# tinynano.net
KiCad netlist of a schematic drawn in Altium Designer
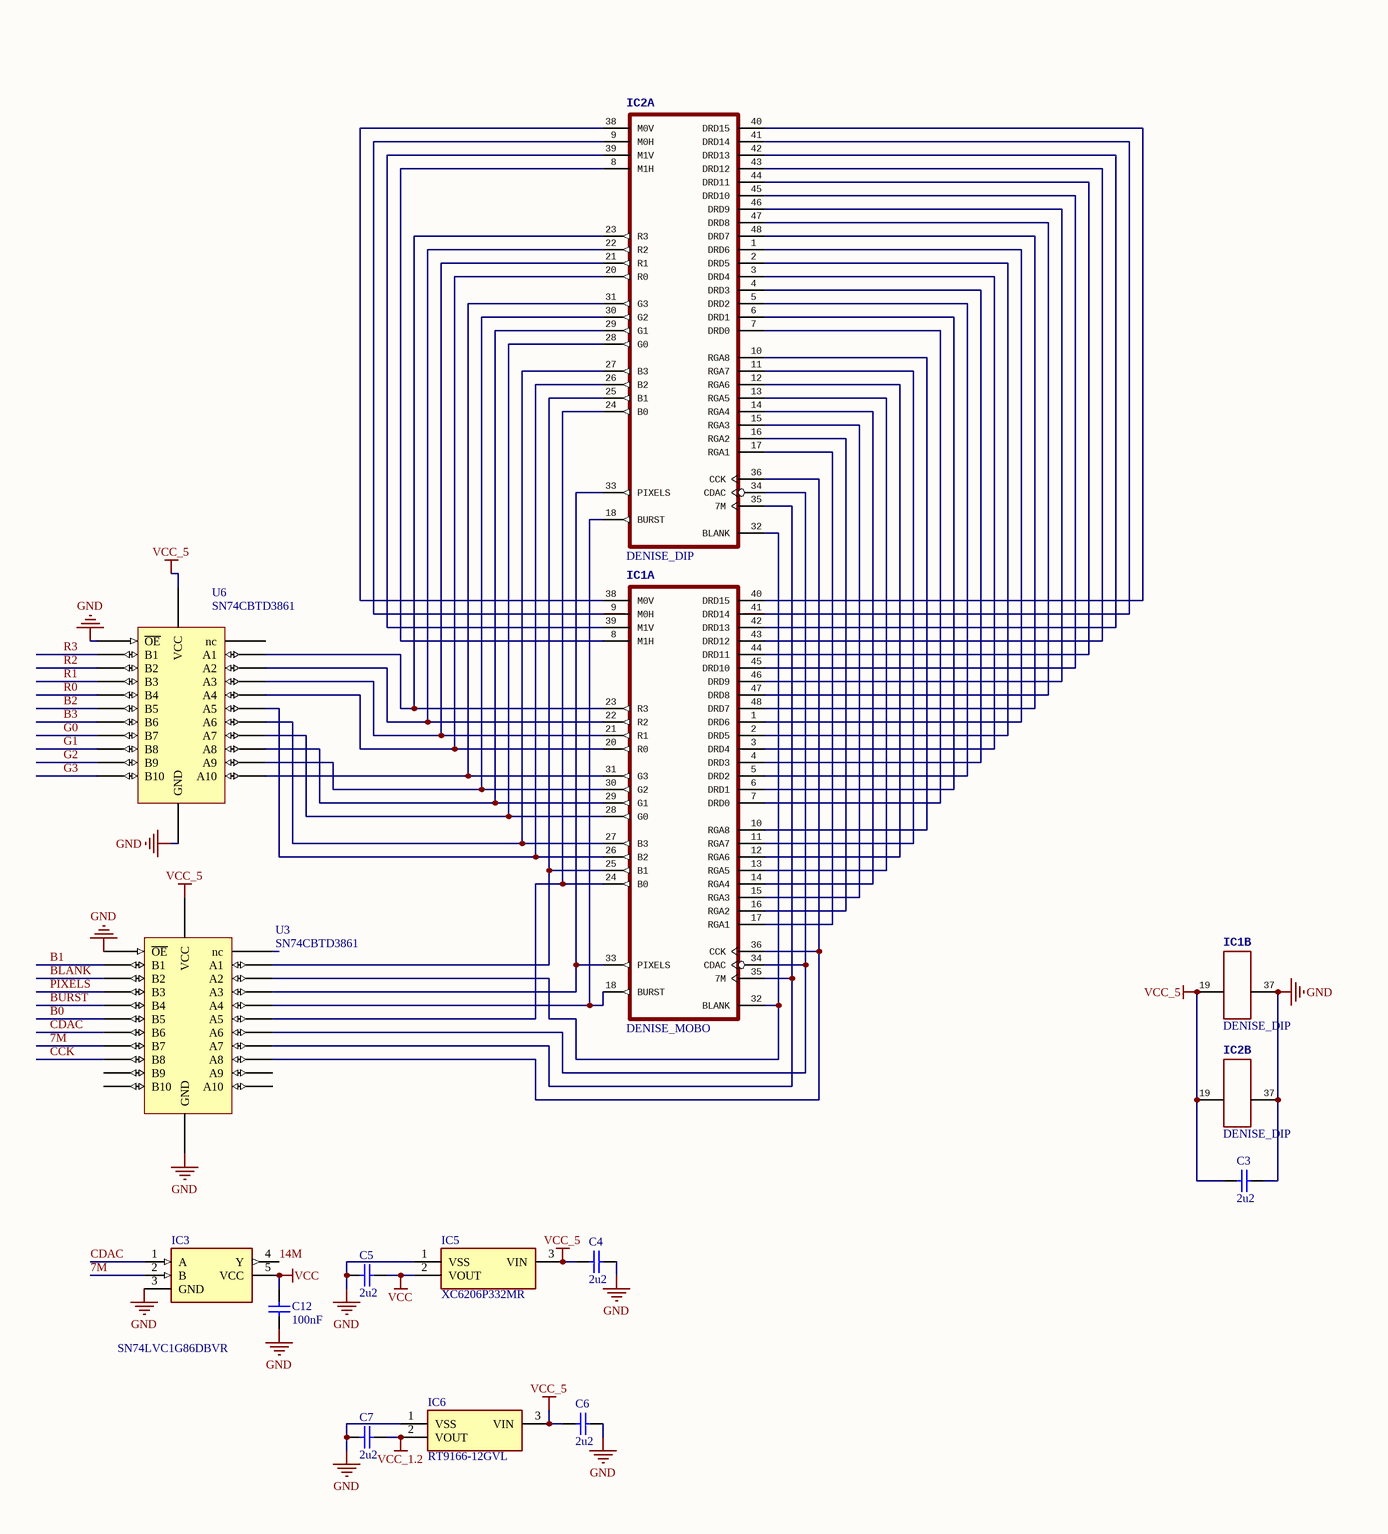
[diagram p0: tinynano.SchDoc, left]
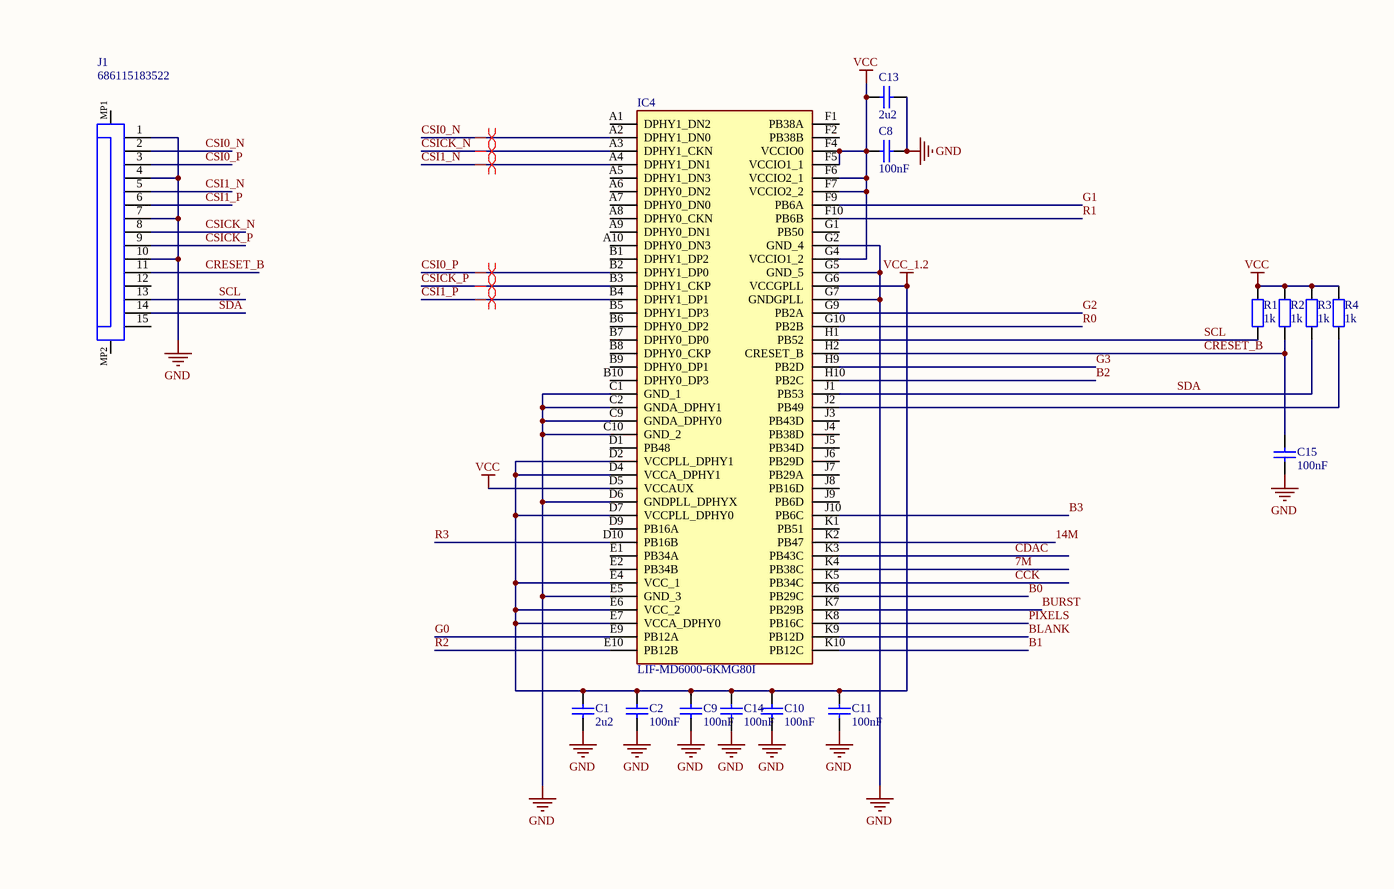
[diagram p1: tinynano.SchDoc, right]

(export (version "E")
  (design (tool "Eeschema 10.0.6"))
  (components
    (comp (ref "C1")
      (value "2u2")
      (footprint "1608[0603]")
      (description "Capacitor (Semiconductor SIM Model)")
      (fields (field (name "Comment") "Cap Semi") (field (name "PUBLISHER") "Altium Limited"))
      (libsource (lib "Miscellaneous Devices") (part "Cap Semi"))
    )
    (comp (ref "C2")
      (value "100nF")
      (footprint "0402")
      (description "Capacitor (Semiconductor SIM Model)")
      (fields (field (name "Comment") "Cap Semi") (field (name "PUBLISHER") "Altium Limited"))
      (libsource (lib "Miscellaneous Devices") (part "Cap Semi"))
    )
    (comp (ref "C3")
      (value "2u2")
      (footprint "1608[0603]")
      (description "Capacitor (Semiconductor SIM Model)")
      (fields (field (name "Comment") "Cap Semi") (field (name "PUBLISHER") "Altium Limited"))
      (libsource (lib "Miscellaneous Devices") (part "Cap Semi"))
    )
    (comp (ref "C4")
      (value "2u2")
      (footprint "1608[0603]")
      (description "Capacitor (Semiconductor SIM Model)")
      (fields (field (name "Comment") "Cap Semi") (field (name "PUBLISHER") "Altium Limited"))
      (libsource (lib "Miscellaneous Devices") (part "Cap Semi"))
    )
    (comp (ref "C5")
      (value "2u2")
      (footprint "1608[0603]")
      (description "Capacitor (Semiconductor SIM Model)")
      (fields (field (name "Comment") "Cap Semi") (field (name "PUBLISHER") "Altium Limited"))
      (libsource (lib "Miscellaneous Devices") (part "Cap Semi"))
    )
    (comp (ref "C6")
      (value "2u2")
      (footprint "1608[0603]")
      (description "Capacitor (Semiconductor SIM Model)")
      (fields (field (name "Comment") "Cap Semi") (field (name "PUBLISHER") "Altium Limited"))
      (libsource (lib "Miscellaneous Devices") (part "Cap Semi"))
    )
    (comp (ref "C7")
      (value "2u2")
      (footprint "1608[0603]")
      (description "Capacitor (Semiconductor SIM Model)")
      (fields (field (name "Comment") "Cap Semi") (field (name "PUBLISHER") "Altium Limited"))
      (libsource (lib "Miscellaneous Devices") (part "Cap Semi"))
    )
    (comp (ref "C8")
      (value "100nF")
      (footprint "0402")
      (description "Capacitor (Semiconductor SIM Model)")
      (fields (field (name "Comment") "Cap Semi") (field (name "PUBLISHER") "Altium Limited"))
      (libsource (lib "Miscellaneous Devices") (part "Cap Semi"))
    )
    (comp (ref "C9")
      (value "100nF")
      (footprint "0402")
      (description "Capacitor (Semiconductor SIM Model)")
      (fields (field (name "Comment") "Cap Semi") (field (name "PUBLISHER") "Altium Limited"))
      (libsource (lib "Miscellaneous Devices") (part "Cap Semi"))
    )
    (comp (ref "C10")
      (value "100nF")
      (footprint "0402")
      (description "Capacitor (Semiconductor SIM Model)")
      (fields (field (name "Comment") "Cap Semi") (field (name "PUBLISHER") "Altium Limited"))
      (libsource (lib "Miscellaneous Devices") (part "Cap Semi"))
    )
    (comp (ref "C11")
      (value "100nF")
      (footprint "0402")
      (description "Capacitor (Semiconductor SIM Model)")
      (fields (field (name "Comment") "Cap Semi") (field (name "PUBLISHER") "Altium Limited"))
      (libsource (lib "Miscellaneous Devices") (part "Cap Semi"))
    )
    (comp (ref "C12")
      (value "100nF")
      (footprint "0402")
      (description "Capacitor (Semiconductor SIM Model)")
      (fields (field (name "Comment") "Cap Semi") (field (name "PUBLISHER") "Altium Limited"))
      (libsource (lib "Miscellaneous Devices") (part "Cap Semi"))
    )
    (comp (ref "C13")
      (value "2u2")
      (footprint "1608[0603]")
      (description "Capacitor (Semiconductor SIM Model)")
      (fields (field (name "Comment") "Cap Semi") (field (name "PUBLISHER") "Altium Limited"))
      (libsource (lib "Miscellaneous Devices") (part "Cap Semi"))
    )
    (comp (ref "C14")
      (value "100nF")
      (footprint "1608[0603]")
      (description "Capacitor (Semiconductor SIM Model)")
      (fields (field (name "Comment") "Cap Semi") (field (name "PUBLISHER") "Altium Limited"))
      (libsource (lib "Miscellaneous Devices") (part "Cap Semi"))
    )
    (comp (ref "C15")
      (value "100nF")
      (footprint "0402")
      (description "Capacitor (Semiconductor SIM Model)")
      (fields (field (name "Comment") "Cap Semi") (field (name "PUBLISHER") "Altium Limited"))
      (libsource (lib "Miscellaneous Devices") (part "Cap Semi"))
    )
    (comp (ref "IC1")
      (value "DENISE_MOBO")
      (footprint "DIP48-6")
      (libsource (lib "Amiga") (part "DENISE_DIP"))
    )
    (comp (ref "IC2")
      (value "DENISE_DIP")
      (footprint "DIP48-6")
      (libsource (lib "Amiga") (part "DENISE_DIP"))
    )
    (comp (ref "IC3")
      (value "SN74LVC1G86DBVR")
      (footprint "SamacSys:SOT95P280X145-5N")
      (description "Integrated Circuit")
      (fields (field (name "MOUSER PART NUMBER") "595-SN74LVC1G86DBVR"))
      (libsource (lib "*") (part "SN74LVC1G86DBVR"))
    )
    (comp (ref "IC4")
      (value "LIF-MD6000-6KMG80I")
      (footprint "SamacSys:BGA80C65P10X10_700X700X120")
      (description "Integrated Circuit")
      (fields (field (name "MOUSER PART NUMBER") "842-LIFMD60006KMG80I"))
      (libsource (lib "*") (part "LIF-MD6000-6KMG80I"))
    )
    (comp (ref "IC5")
      (value "XC6206P332MR")
      (footprint "SamacSys:SOT95P280X130-3N")
      (description "Integrated Circuit")
      (libsource (lib "*") (part "XC6206P332MR"))
    )
    (comp (ref "IC6")
      (value "RT9166-12GVL")
      (footprint "SamacSys:SOT95P280X130-3N")
      (description "Integrated Circuit")
      (fields (field (name "MANUFACTURER_PART_NUMBER") "XC6206P332MR"))
      (libsource (lib "*") (part "XC6206P332MR"))
    )
    (comp (ref "J1")
      (value "686115183522")
      (footprint "686115183522")
      (description "WR-FPC SMT ZIF Horizontal Bottom Contact Low Profile, pitch 1mm, 15p")
      (fields (field (name "MANUFACTURER") "Wurth Elektronik"))
      (libsource (lib "Altium_WR-FPC (rev21a)") (part "686115183522"))
    )
    (comp (ref "R1")
      (value "1k")
      (footprint "0402-A")
      (description "Resistor")
      (fields (field (name "Comment") "Res2") (field (name "PUBLISHER") "Altium Limited"))
      (libsource (lib "Miscellaneous Devices") (part "Res2"))
    )
    (comp (ref "R2")
      (value "1k")
      (footprint "0402-A")
      (description "Resistor")
      (fields (field (name "Comment") "Res2") (field (name "PUBLISHER") "Altium Limited"))
      (libsource (lib "Miscellaneous Devices") (part "Res2"))
    )
    (comp (ref "R3")
      (value "1k")
      (footprint "0402-A")
      (description "Resistor")
      (fields (field (name "Comment") "Res2") (field (name "PUBLISHER") "Altium Limited"))
      (libsource (lib "Miscellaneous Devices") (part "Res2"))
    )
    (comp (ref "R4")
      (value "1k")
      (footprint "0402-A")
      (description "Resistor")
      (fields (field (name "Comment") "Res2") (field (name "PUBLISHER") "Altium Limited"))
      (libsource (lib "Miscellaneous Devices") (part "Res2"))
    )
    (comp (ref "U3")
      (value "SN74CBTD3861")
      (footprint "DB024")
      (description "10-bit FET bus level shifting switch")
      (libsource (lib "7Robot") (part "SN74CBTD3861"))
    )
    (comp (ref "U6")
      (value "SN74CBTD3861")
      (footprint "DB024")
      (description "10-bit FET bus level shifting switch")
      (libsource (lib "7Robot") (part "SN74CBTD3861"))
    )
  )
  (nets
    (net (code "1") (name "/7M") (class "Default")
      (node (ref "IC3") (pin "2") (pinfunction "B_2") (pintype "input"))
      (node (ref "IC4") (pin "K4") (pinfunction "PB38C_K4") (pintype "passive"))
      (node (ref "U3") (pin "16") (pinfunction "B7_16") (pintype "bidirectional"))
    )
    (net (code "2") (name "/14M") (class "Default")
      (node (ref "IC3") (pin "4") (pinfunction "Y_4") (pintype "output"))
      (node (ref "IC4") (pin "K2") (pinfunction "PB47_K2") (pintype "passive"))
    )
    (net (code "3") (name "/B0") (class "Default")
      (node (ref "IC4") (pin "K6") (pinfunction "PB29C_K6") (pintype "passive"))
      (node (ref "U3") (pin "18") (pinfunction "B5_18") (pintype "bidirectional"))
    )
    (net (code "4") (name "/B1") (class "Default")
      (node (ref "IC4") (pin "K10") (pinfunction "PB12C_K10") (pintype "passive"))
      (node (ref "U3") (pin "22") (pinfunction "B1_22") (pintype "bidirectional"))
    )
    (net (code "5") (name "/B2") (class "Default")
      (node (ref "IC4") (pin "H10") (pinfunction "PB2C_H10") (pintype "passive"))
      (node (ref "U6") (pin "18") (pinfunction "B5_18") (pintype "bidirectional"))
    )
    (net (code "6") (name "/B3") (class "Default")
      (node (ref "IC4") (pin "J10") (pinfunction "PB6C_J10") (pintype "passive"))
      (node (ref "U6") (pin "17") (pinfunction "B6_17") (pintype "bidirectional"))
    )
    (net (code "7") (name "/BLANK") (class "Default")
      (node (ref "IC4") (pin "K9") (pinfunction "PB12D_K9") (pintype "passive"))
      (node (ref "U3") (pin "21") (pinfunction "B2_21") (pintype "bidirectional"))
    )
    (net (code "8") (name "/BURST") (class "Default")
      (node (ref "IC4") (pin "K7") (pinfunction "PB29B_K7") (pintype "passive"))
      (node (ref "U3") (pin "19") (pinfunction "B4_19") (pintype "bidirectional"))
    )
    (net (code "9") (name "/CCK") (class "Default")
      (node (ref "IC4") (pin "K5") (pinfunction "PB34C_K5") (pintype "passive"))
      (node (ref "U3") (pin "15") (pinfunction "B8_15") (pintype "bidirectional"))
    )
    (net (code "10") (name "/CDAC") (class "Default")
      (node (ref "IC3") (pin "1") (pinfunction "A_1") (pintype "input"))
      (node (ref "IC4") (pin "K3") (pinfunction "PB43C_K3") (pintype "passive"))
      (node (ref "U3") (pin "17") (pinfunction "B6_17") (pintype "bidirectional"))
    )
    (net (code "11") (name "/CRESET_B") (class "Default")
      (node (ref "C15") (pin "2") (pinfunction "2_2") (pintype "passive"))
      (node (ref "IC4") (pin "H2") (pinfunction "CRESET_B_H2") (pintype "passive"))
      (node (ref "J1") (pin "11") (pinfunction "11_11") (pintype "passive"))
      (node (ref "R2") (pin "2") (pinfunction "2_2") (pintype "passive"))
    )
    (net (code "12") (name "/CSI0_N") (class "Default")
      (node (ref "IC4") (pin "A2") (pinfunction "DPHY1_DN0_A2") (pintype "passive"))
      (node (ref "J1") (pin "2") (pinfunction "2_2") (pintype "passive"))
    )
    (net (code "13") (name "/CSI0_P") (class "Default")
      (node (ref "IC4") (pin "B2") (pinfunction "DPHY1_DP0_B2") (pintype "passive"))
      (node (ref "J1") (pin "3") (pinfunction "3_3") (pintype "passive"))
    )
    (net (code "14") (name "/CSI1_N") (class "Default")
      (node (ref "IC4") (pin "A4") (pinfunction "DPHY1_DN1_A4") (pintype "passive"))
      (node (ref "J1") (pin "5") (pinfunction "5_5") (pintype "passive"))
    )
    (net (code "15") (name "/CSI1_P") (class "Default")
      (node (ref "IC4") (pin "B4") (pinfunction "DPHY1_DP1_B4") (pintype "passive"))
      (node (ref "J1") (pin "6") (pinfunction "6_6") (pintype "passive"))
    )
    (net (code "16") (name "/CSICK_N") (class "Default")
      (node (ref "IC4") (pin "A3") (pinfunction "DPHY1_CKN_A3") (pintype "passive"))
      (node (ref "J1") (pin "8") (pinfunction "8_8") (pintype "passive"))
    )
    (net (code "17") (name "/CSICK_P") (class "Default")
      (node (ref "IC4") (pin "B3") (pinfunction "DPHY1_CKP_B3") (pintype "passive"))
      (node (ref "J1") (pin "9") (pinfunction "9_9") (pintype "passive"))
    )
    (net (code "18") (name "/G0") (class "Default")
      (node (ref "IC4") (pin "E9") (pinfunction "PB12A_E9") (pintype "passive"))
      (node (ref "U6") (pin "16") (pinfunction "B7_16") (pintype "bidirectional"))
    )
    (net (code "19") (name "/G1") (class "Default")
      (node (ref "IC4") (pin "F9") (pinfunction "PB6A_F9") (pintype "passive"))
      (node (ref "U6") (pin "15") (pinfunction "B8_15") (pintype "bidirectional"))
    )
    (net (code "20") (name "/G2") (class "Default")
      (node (ref "IC4") (pin "G9") (pinfunction "PB2A_G9") (pintype "passive"))
      (node (ref "U6") (pin "14") (pinfunction "B9_14") (pintype "bidirectional"))
    )
    (net (code "21") (name "/G3") (class "Default")
      (node (ref "IC4") (pin "H9") (pinfunction "PB2D_H9") (pintype "passive"))
      (node (ref "U6") (pin "13") (pinfunction "B10_13") (pintype "bidirectional"))
    )
    (net (code "22") (name "/PIXELS") (class "Default")
      (node (ref "IC4") (pin "K8") (pinfunction "PB16C_K8") (pintype "passive"))
      (node (ref "U3") (pin "20") (pinfunction "B3_20") (pintype "bidirectional"))
    )
    (net (code "23") (name "/R0") (class "Default")
      (node (ref "IC4") (pin "G10") (pinfunction "PB2B_G10") (pintype "passive"))
      (node (ref "U6") (pin "19") (pinfunction "B4_19") (pintype "bidirectional"))
    )
    (net (code "24") (name "/R1") (class "Default")
      (node (ref "IC4") (pin "F10") (pinfunction "PB6B_F10") (pintype "passive"))
      (node (ref "U6") (pin "20") (pinfunction "B3_20") (pintype "bidirectional"))
    )
    (net (code "25") (name "/R2") (class "Default")
      (node (ref "IC4") (pin "E10") (pinfunction "PB12B_E10") (pintype "passive"))
      (node (ref "U6") (pin "21") (pinfunction "B2_21") (pintype "bidirectional"))
    )
    (net (code "26") (name "/R3") (class "Default")
      (node (ref "IC4") (pin "D10") (pinfunction "PB16B_D10") (pintype "passive"))
      (node (ref "U6") (pin "22") (pinfunction "B1_22") (pintype "bidirectional"))
    )
    (net (code "27") (name "/SCL") (class "Default")
      (node (ref "IC4") (pin "H1") (pinfunction "PB52_H1") (pintype "passive"))
      (node (ref "J1") (pin "13") (pinfunction "13_13") (pintype "passive"))
      (node (ref "R1") (pin "2") (pinfunction "2_2") (pintype "passive"))
    )
    (net (code "28") (name "/SDA") (class "Default")
      (node (ref "IC4") (pin "J1") (pinfunction "PB53_J1") (pintype "passive"))
      (node (ref "J1") (pin "14") (pinfunction "14_14") (pintype "passive"))
      (node (ref "R3") (pin "2") (pinfunction "2_2") (pintype "passive"))
    )
    (net (code "29") (name "GND") (class "Default")
      (node (ref "C1") (pin "2") (pinfunction "2_2") (pintype "passive"))
      (node (ref "C10") (pin "1") (pinfunction "1_1") (pintype "passive"))
      (node (ref "C11") (pin "1") (pinfunction "1_1") (pintype "passive"))
      (node (ref "C12") (pin "1") (pinfunction "1_1") (pintype "passive"))
      (node (ref "C13") (pin "2") (pinfunction "2_2") (pintype "passive"))
      (node (ref "C14") (pin "1") (pinfunction "1_1") (pintype "passive"))
      (node (ref "C15") (pin "1") (pinfunction "1_1") (pintype "passive"))
      (node (ref "C2") (pin "1") (pinfunction "1_1") (pintype "passive"))
      (node (ref "C3") (pin "1") (pinfunction "1_1") (pintype "passive"))
      (node (ref "C4") (pin "1") (pinfunction "1_1") (pintype "passive"))
      (node (ref "C5") (pin "2") (pinfunction "2_2") (pintype "passive"))
      (node (ref "C6") (pin "1") (pinfunction "1_1") (pintype "passive"))
      (node (ref "C7") (pin "2") (pinfunction "2_2") (pintype "passive"))
      (node (ref "C8") (pin "1") (pinfunction "1_1") (pintype "passive"))
      (node (ref "C9") (pin "1") (pinfunction "1_1") (pintype "passive"))
      (node (ref "IC1") (pin "37") (pinfunction "GND1_37") (pintype "power_in"))
      (node (ref "IC2") (pin "37") (pinfunction "GND1_37") (pintype "power_in"))
      (node (ref "IC3") (pin "3") (pinfunction "GND_3") (pintype "power_in"))
      (node (ref "IC4") (pin "C1") (pinfunction "GND_1_C1") (pintype "passive"))
      (node (ref "IC4") (pin "C10") (pinfunction "GND_2_C10") (pintype "passive"))
      (node (ref "IC4") (pin "C2") (pinfunction "GNDA_DPHY1_C2") (pintype "passive"))
      (node (ref "IC4") (pin "C9") (pinfunction "GNDA_DPHY0_C9") (pintype "passive"))
      (node (ref "IC4") (pin "D6") (pinfunction "GNDPLL_DPHYX_D6") (pintype "passive"))
      (node (ref "IC4") (pin "E5") (pinfunction "GND_3_E5") (pintype "passive"))
      (node (ref "IC4") (pin "G2") (pinfunction "GND_4_G2") (pintype "passive"))
      (node (ref "IC4") (pin "G5") (pinfunction "GND_5_G5") (pintype "passive"))
      (node (ref "IC4") (pin "G7") (pinfunction "GNDGPLL_G7") (pintype "passive"))
      (node (ref "IC5") (pin "1") (pinfunction "VSS_1") (pintype "passive"))
      (node (ref "IC6") (pin "1") (pinfunction "VSS_1") (pintype "passive"))
      (node (ref "J1") (pin "1") (pinfunction "1_1") (pintype "passive"))
      (node (ref "J1") (pin "10") (pinfunction "10_10") (pintype "passive"))
      (node (ref "J1") (pin "4") (pinfunction "4_4") (pintype "passive"))
      (node (ref "J1") (pin "7") (pinfunction "7_7") (pintype "passive"))
      (node (ref "U3") (pin "12") (pinfunction "GND_12") (pintype "power_in"))
      (node (ref "U3") (pin "23") (pinfunction "~{OE}_23") (pintype "input"))
      (node (ref "U6") (pin "12") (pinfunction "GND_12") (pintype "power_in"))
      (node (ref "U6") (pin "23") (pinfunction "~{OE}_23") (pintype "input"))
    )
    (net (code "30") (name "Net-(IC1A-7M)") (class "Default")
      (node (ref "IC1") (pin "35") (pinfunction "7M_35") (pintype "passive"))
      (node (ref "IC2") (pin "35") (pinfunction "7M_35") (pintype "passive"))
      (node (ref "U3") (pin "8") (pinfunction "A7_8") (pintype "bidirectional"))
    )
    (net (code "31") (name "Net-(IC1A-B0)") (class "Default")
      (node (ref "IC1") (pin "24") (pinfunction "B0_24") (pintype "output"))
      (node (ref "IC2") (pin "24") (pinfunction "B0_24") (pintype "output"))
      (node (ref "U3") (pin "6") (pinfunction "A5_6") (pintype "bidirectional"))
    )
    (net (code "32") (name "Net-(IC1A-B1)") (class "Default")
      (node (ref "IC1") (pin "25") (pinfunction "B1_25") (pintype "output"))
      (node (ref "IC2") (pin "25") (pinfunction "B1_25") (pintype "output"))
      (node (ref "U3") (pin "2") (pinfunction "A1_2") (pintype "bidirectional"))
    )
    (net (code "33") (name "Net-(IC1A-B2)") (class "Default")
      (node (ref "IC1") (pin "26") (pinfunction "B2_26") (pintype "output"))
      (node (ref "IC2") (pin "26") (pinfunction "B2_26") (pintype "output"))
      (node (ref "U6") (pin "6") (pinfunction "A5_6") (pintype "bidirectional"))
    )
    (net (code "34") (name "Net-(IC1A-B3)") (class "Default")
      (node (ref "IC1") (pin "27") (pinfunction "B3_27") (pintype "output"))
      (node (ref "IC2") (pin "27") (pinfunction "B3_27") (pintype "output"))
      (node (ref "U6") (pin "7") (pinfunction "A6_7") (pintype "bidirectional"))
    )
    (net (code "35") (name "Net-(IC1A-BLANK)") (class "Default")
      (node (ref "IC1") (pin "32") (pinfunction "BLANK_32") (pintype "passive"))
      (node (ref "IC2") (pin "32") (pinfunction "BLANK_32") (pintype "passive"))
      (node (ref "U3") (pin "3") (pinfunction "A2_3") (pintype "bidirectional"))
    )
    (net (code "36") (name "Net-(IC1A-BURST)") (class "Default")
      (node (ref "IC1") (pin "18") (pinfunction "BURST_18") (pintype "output"))
      (node (ref "IC2") (pin "18") (pinfunction "BURST_18") (pintype "output"))
      (node (ref "U3") (pin "5") (pinfunction "A4_5") (pintype "bidirectional"))
    )
    (net (code "37") (name "Net-(IC1A-CCK)") (class "Default")
      (node (ref "IC1") (pin "36") (pinfunction "CCK_36") (pintype "passive"))
      (node (ref "IC2") (pin "36") (pinfunction "CCK_36") (pintype "passive"))
      (node (ref "U3") (pin "9") (pinfunction "A8_9") (pintype "bidirectional"))
    )
    (net (code "38") (name "Net-(IC1A-CDAC)") (class "Default")
      (node (ref "IC1") (pin "34") (pinfunction "CDAC_34") (pintype "passive"))
      (node (ref "IC2") (pin "34") (pinfunction "CDAC_34") (pintype "passive"))
      (node (ref "U3") (pin "7") (pinfunction "A6_7") (pintype "bidirectional"))
    )
    (net (code "39") (name "Net-(IC1A-DRD0)") (class "Default")
      (node (ref "IC1") (pin "7") (pinfunction "DRD0_7") (pintype "passive"))
      (node (ref "IC2") (pin "7") (pinfunction "DRD0_7") (pintype "passive"))
    )
    (net (code "40") (name "Net-(IC1A-DRD1)") (class "Default")
      (node (ref "IC1") (pin "6") (pinfunction "DRD1_6") (pintype "passive"))
      (node (ref "IC2") (pin "6") (pinfunction "DRD1_6") (pintype "passive"))
    )
    (net (code "41") (name "Net-(IC1A-DRD2)") (class "Default")
      (node (ref "IC1") (pin "5") (pinfunction "DRD2_5") (pintype "passive"))
      (node (ref "IC2") (pin "5") (pinfunction "DRD2_5") (pintype "passive"))
    )
    (net (code "42") (name "Net-(IC1A-DRD3)") (class "Default")
      (node (ref "IC1") (pin "4") (pinfunction "DRD3_4") (pintype "passive"))
      (node (ref "IC2") (pin "4") (pinfunction "DRD3_4") (pintype "passive"))
    )
    (net (code "43") (name "Net-(IC1A-DRD4)") (class "Default")
      (node (ref "IC1") (pin "3") (pinfunction "DRD4_3") (pintype "passive"))
      (node (ref "IC2") (pin "3") (pinfunction "DRD4_3") (pintype "passive"))
    )
    (net (code "44") (name "Net-(IC1A-DRD5)") (class "Default")
      (node (ref "IC1") (pin "2") (pinfunction "DRD5_2") (pintype "passive"))
      (node (ref "IC2") (pin "2") (pinfunction "DRD5_2") (pintype "passive"))
    )
    (net (code "45") (name "Net-(IC1A-DRD6)") (class "Default")
      (node (ref "IC1") (pin "1") (pinfunction "DRD6_1") (pintype "passive"))
      (node (ref "IC2") (pin "1") (pinfunction "DRD6_1") (pintype "passive"))
    )
    (net (code "46") (name "Net-(IC1A-DRD7)") (class "Default")
      (node (ref "IC1") (pin "48") (pinfunction "DRD7_48") (pintype "passive"))
      (node (ref "IC2") (pin "48") (pinfunction "DRD7_48") (pintype "passive"))
    )
    (net (code "47") (name "Net-(IC1A-DRD8)") (class "Default")
      (node (ref "IC1") (pin "47") (pinfunction "DRD8_47") (pintype "passive"))
      (node (ref "IC2") (pin "47") (pinfunction "DRD8_47") (pintype "passive"))
    )
    (net (code "48") (name "Net-(IC1A-DRD9)") (class "Default")
      (node (ref "IC1") (pin "46") (pinfunction "DRD9_46") (pintype "passive"))
      (node (ref "IC2") (pin "46") (pinfunction "DRD9_46") (pintype "passive"))
    )
    (net (code "49") (name "Net-(IC1A-DRD10)") (class "Default")
      (node (ref "IC1") (pin "45") (pinfunction "DRD10_45") (pintype "passive"))
      (node (ref "IC2") (pin "45") (pinfunction "DRD10_45") (pintype "passive"))
    )
    (net (code "50") (name "Net-(IC1A-DRD11)") (class "Default")
      (node (ref "IC1") (pin "44") (pinfunction "DRD11_44") (pintype "passive"))
      (node (ref "IC2") (pin "44") (pinfunction "DRD11_44") (pintype "passive"))
    )
    (net (code "51") (name "Net-(IC1A-DRD12)") (class "Default")
      (node (ref "IC1") (pin "43") (pinfunction "DRD12_43") (pintype "passive"))
      (node (ref "IC2") (pin "43") (pinfunction "DRD12_43") (pintype "passive"))
    )
    (net (code "52") (name "Net-(IC1A-DRD13)") (class "Default")
      (node (ref "IC1") (pin "42") (pinfunction "DRD13_42") (pintype "passive"))
      (node (ref "IC2") (pin "42") (pinfunction "DRD13_42") (pintype "passive"))
    )
    (net (code "53") (name "Net-(IC1A-DRD14)") (class "Default")
      (node (ref "IC1") (pin "41") (pinfunction "DRD14_41") (pintype "passive"))
      (node (ref "IC2") (pin "41") (pinfunction "DRD14_41") (pintype "passive"))
    )
    (net (code "54") (name "Net-(IC1A-DRD15)") (class "Default")
      (node (ref "IC1") (pin "40") (pinfunction "DRD15_40") (pintype "passive"))
      (node (ref "IC2") (pin "40") (pinfunction "DRD15_40") (pintype "passive"))
    )
    (net (code "55") (name "Net-(IC1A-G0)") (class "Default")
      (node (ref "IC1") (pin "28") (pinfunction "G0_28") (pintype "output"))
      (node (ref "IC2") (pin "28") (pinfunction "G0_28") (pintype "output"))
      (node (ref "U6") (pin "8") (pinfunction "A7_8") (pintype "bidirectional"))
    )
    (net (code "56") (name "Net-(IC1A-G1)") (class "Default")
      (node (ref "IC1") (pin "29") (pinfunction "G1_29") (pintype "output"))
      (node (ref "IC2") (pin "29") (pinfunction "G1_29") (pintype "output"))
      (node (ref "U6") (pin "9") (pinfunction "A8_9") (pintype "bidirectional"))
    )
    (net (code "57") (name "Net-(IC1A-G2)") (class "Default")
      (node (ref "IC1") (pin "30") (pinfunction "G2_30") (pintype "output"))
      (node (ref "IC2") (pin "30") (pinfunction "G2_30") (pintype "output"))
      (node (ref "U6") (pin "10") (pinfunction "A9_10") (pintype "bidirectional"))
    )
    (net (code "58") (name "Net-(IC1A-G3)") (class "Default")
      (node (ref "IC1") (pin "31") (pinfunction "G3_31") (pintype "output"))
      (node (ref "IC2") (pin "31") (pinfunction "G3_31") (pintype "output"))
      (node (ref "U6") (pin "11") (pinfunction "A10_11") (pintype "bidirectional"))
    )
    (net (code "59") (name "Net-(IC1A-M0H)") (class "Default")
      (node (ref "IC1") (pin "9") (pinfunction "M0H_9") (pintype "passive"))
      (node (ref "IC2") (pin "9") (pinfunction "M0H_9") (pintype "passive"))
    )
    (net (code "60") (name "Net-(IC1A-M0V)") (class "Default")
      (node (ref "IC1") (pin "38") (pinfunction "M0V_38") (pintype "passive"))
      (node (ref "IC2") (pin "38") (pinfunction "M0V_38") (pintype "passive"))
    )
    (net (code "61") (name "Net-(IC1A-M1H)") (class "Default")
      (node (ref "IC1") (pin "8") (pinfunction "M1H_8") (pintype "passive"))
      (node (ref "IC2") (pin "8") (pinfunction "M1H_8") (pintype "passive"))
    )
    (net (code "62") (name "Net-(IC1A-M1V)") (class "Default")
      (node (ref "IC1") (pin "39") (pinfunction "M1V_39") (pintype "passive"))
      (node (ref "IC2") (pin "39") (pinfunction "M1V_39") (pintype "passive"))
    )
    (net (code "63") (name "Net-(IC1A-PIXELS)") (class "Default")
      (node (ref "IC1") (pin "33") (pinfunction "PIXELS_33") (pintype "output"))
      (node (ref "IC2") (pin "33") (pinfunction "PIXELS_33") (pintype "output"))
      (node (ref "U3") (pin "4") (pinfunction "A3_4") (pintype "bidirectional"))
    )
    (net (code "64") (name "Net-(IC1A-R0)") (class "Default")
      (node (ref "IC1") (pin "20") (pinfunction "R0_20") (pintype "output"))
      (node (ref "IC2") (pin "20") (pinfunction "R0_20") (pintype "output"))
      (node (ref "U6") (pin "5") (pinfunction "A4_5") (pintype "bidirectional"))
    )
    (net (code "65") (name "Net-(IC1A-R1)") (class "Default")
      (node (ref "IC1") (pin "21") (pinfunction "R1_21") (pintype "output"))
      (node (ref "IC2") (pin "21") (pinfunction "R1_21") (pintype "output"))
      (node (ref "U6") (pin "4") (pinfunction "A3_4") (pintype "bidirectional"))
    )
    (net (code "66") (name "Net-(IC1A-R2)") (class "Default")
      (node (ref "IC1") (pin "22") (pinfunction "R2_22") (pintype "output"))
      (node (ref "IC2") (pin "22") (pinfunction "R2_22") (pintype "output"))
      (node (ref "U6") (pin "3") (pinfunction "A2_3") (pintype "bidirectional"))
    )
    (net (code "67") (name "Net-(IC1A-R3)") (class "Default")
      (node (ref "IC1") (pin "23") (pinfunction "R3_23") (pintype "output"))
      (node (ref "IC2") (pin "23") (pinfunction "R3_23") (pintype "output"))
      (node (ref "U6") (pin "2") (pinfunction "A1_2") (pintype "bidirectional"))
    )
    (net (code "68") (name "Net-(IC1A-RGA1)") (class "Default")
      (node (ref "IC1") (pin "17") (pinfunction "RGA1_17") (pintype "passive"))
      (node (ref "IC2") (pin "17") (pinfunction "RGA1_17") (pintype "passive"))
    )
    (net (code "69") (name "Net-(IC1A-RGA2)") (class "Default")
      (node (ref "IC1") (pin "16") (pinfunction "RGA2_16") (pintype "passive"))
      (node (ref "IC2") (pin "16") (pinfunction "RGA2_16") (pintype "passive"))
    )
    (net (code "70") (name "Net-(IC1A-RGA3)") (class "Default")
      (node (ref "IC1") (pin "15") (pinfunction "RGA3_15") (pintype "passive"))
      (node (ref "IC2") (pin "15") (pinfunction "RGA3_15") (pintype "passive"))
    )
    (net (code "71") (name "Net-(IC1A-RGA4)") (class "Default")
      (node (ref "IC1") (pin "14") (pinfunction "RGA4_14") (pintype "passive"))
      (node (ref "IC2") (pin "14") (pinfunction "RGA4_14") (pintype "passive"))
    )
    (net (code "72") (name "Net-(IC1A-RGA5)") (class "Default")
      (node (ref "IC1") (pin "13") (pinfunction "RGA5_13") (pintype "passive"))
      (node (ref "IC2") (pin "13") (pinfunction "RGA5_13") (pintype "passive"))
    )
    (net (code "73") (name "Net-(IC1A-RGA6)") (class "Default")
      (node (ref "IC1") (pin "12") (pinfunction "RGA6_12") (pintype "passive"))
      (node (ref "IC2") (pin "12") (pinfunction "RGA6_12") (pintype "passive"))
    )
    (net (code "74") (name "Net-(IC1A-RGA7)") (class "Default")
      (node (ref "IC1") (pin "11") (pinfunction "RGA7_11") (pintype "passive"))
      (node (ref "IC2") (pin "11") (pinfunction "RGA7_11") (pintype "passive"))
    )
    (net (code "75") (name "Net-(IC1A-RGA8)") (class "Default")
      (node (ref "IC1") (pin "10") (pinfunction "RGA8_10") (pintype "passive"))
      (node (ref "IC2") (pin "10") (pinfunction "RGA8_10") (pintype "passive"))
    )
    (net (code "76") (name "Net-(IC4-PB49)") (class "Default")
      (node (ref "IC4") (pin "J2") (pinfunction "PB49_J2") (pintype "passive"))
      (node (ref "R4") (pin "2") (pinfunction "2_2") (pintype "passive"))
    )
    (net (code "77") (name "VCC") (class "Default")
      (node (ref "C12") (pin "2") (pinfunction "2_2") (pintype "passive"))
      (node (ref "C13") (pin "1") (pinfunction "1_1") (pintype "passive"))
      (node (ref "C5") (pin "1") (pinfunction "1_1") (pintype "passive"))
      (node (ref "C8") (pin "2") (pinfunction "2_2") (pintype "passive"))
      (node (ref "IC3") (pin "5") (pinfunction "VCC_5") (pintype "power_in"))
      (node (ref "IC4") (pin "D5") (pinfunction "VCCAUX_D5") (pintype "passive"))
      (node (ref "IC4") (pin "F4") (pinfunction "VCCIO0_F4") (pintype "passive"))
      (node (ref "IC4") (pin "F5") (pinfunction "VCCIO1_1_F5") (pintype "passive"))
      (node (ref "IC4") (pin "F6") (pinfunction "VCCIO2_1_F6") (pintype "passive"))
      (node (ref "IC4") (pin "F7") (pinfunction "VCCIO2_2_F7") (pintype "passive"))
      (node (ref "IC4") (pin "G4") (pinfunction "VCCIO1_2_G4") (pintype "passive"))
      (node (ref "IC5") (pin "2") (pinfunction "VOUT_2") (pintype "passive"))
      (node (ref "R1") (pin "1") (pinfunction "1_1") (pintype "passive"))
      (node (ref "R2") (pin "1") (pinfunction "1_1") (pintype "passive"))
      (node (ref "R3") (pin "1") (pinfunction "1_1") (pintype "passive"))
      (node (ref "R4") (pin "1") (pinfunction "1_1") (pintype "passive"))
    )
    (net (code "78") (name "VCC_1.2") (class "Default")
      (node (ref "C1") (pin "1") (pinfunction "1_1") (pintype "passive"))
      (node (ref "C10") (pin "2") (pinfunction "2_2") (pintype "passive"))
      (node (ref "C11") (pin "2") (pinfunction "2_2") (pintype "passive"))
      (node (ref "C14") (pin "2") (pinfunction "2_2") (pintype "passive"))
      (node (ref "C2") (pin "2") (pinfunction "2_2") (pintype "passive"))
      (node (ref "C7") (pin "1") (pinfunction "1_1") (pintype "passive"))
      (node (ref "C9") (pin "2") (pinfunction "2_2") (pintype "passive"))
      (node (ref "IC4") (pin "D2") (pinfunction "VCCPLL_DPHY1_D2") (pintype "passive"))
      (node (ref "IC4") (pin "D4") (pinfunction "VCCA_DPHY1_D4") (pintype "passive"))
      (node (ref "IC4") (pin "D7") (pinfunction "VCCPLL_DPHY0_D7") (pintype "passive"))
      (node (ref "IC4") (pin "E4") (pinfunction "VCC_1_E4") (pintype "passive"))
      (node (ref "IC4") (pin "E6") (pinfunction "VCC_2_E6") (pintype "passive"))
      (node (ref "IC4") (pin "E7") (pinfunction "VCCA_DPHY0_E7") (pintype "passive"))
      (node (ref "IC4") (pin "G6") (pinfunction "VCCGPLL_G6") (pintype "passive"))
      (node (ref "IC6") (pin "2") (pinfunction "VOUT_2") (pintype "passive"))
    )
    (net (code "79") (name "VCC_5") (class "Default")
      (node (ref "C3") (pin "2") (pinfunction "2_2") (pintype "passive"))
      (node (ref "C4") (pin "2") (pinfunction "2_2") (pintype "passive"))
      (node (ref "C6") (pin "2") (pinfunction "2_2") (pintype "passive"))
      (node (ref "IC1") (pin "19") (pinfunction "VCC1_19") (pintype "power_in"))
      (node (ref "IC2") (pin "19") (pinfunction "VCC1_19") (pintype "power_in"))
      (node (ref "IC5") (pin "3") (pinfunction "VIN_3") (pintype "passive"))
      (node (ref "IC6") (pin "3") (pinfunction "VIN_3") (pintype "passive"))
      (node (ref "U3") (pin "24") (pinfunction "VCC_24") (pintype "power_in"))
      (node (ref "U6") (pin "24") (pinfunction "VCC_24") (pintype "power_in"))
    )
    (net (code "80") (name "unconnected-(IC4-DPHY0_CKN-PadA8)") (class "Default")
      (node (ref "IC4") (pin "A8") (pinfunction "DPHY0_CKN_A8") (pintype "passive"))
    )
    (net (code "81") (name "unconnected-(IC4-DPHY0_CKP-PadB8)") (class "Default")
      (node (ref "IC4") (pin "B8") (pinfunction "DPHY0_CKP_B8") (pintype "passive"))
    )
    (net (code "82") (name "unconnected-(IC4-DPHY0_DN0-PadA7)") (class "Default")
      (node (ref "IC4") (pin "A7") (pinfunction "DPHY0_DN0_A7") (pintype "passive"))
    )
    (net (code "83") (name "unconnected-(IC4-DPHY0_DN1-PadA9)") (class "Default")
      (node (ref "IC4") (pin "A9") (pinfunction "DPHY0_DN1_A9") (pintype "passive"))
    )
    (net (code "84") (name "unconnected-(IC4-DPHY0_DN2-PadA6)") (class "Default")
      (node (ref "IC4") (pin "A6") (pinfunction "DPHY0_DN2_A6") (pintype "passive"))
    )
    (net (code "85") (name "unconnected-(IC4-DPHY0_DN3-PadA10)") (class "Default")
      (node (ref "IC4") (pin "A10") (pinfunction "DPHY0_DN3_A10") (pintype "passive"))
    )
    (net (code "86") (name "unconnected-(IC4-DPHY0_DP0-PadB7)") (class "Default")
      (node (ref "IC4") (pin "B7") (pinfunction "DPHY0_DP0_B7") (pintype "passive"))
    )
    (net (code "87") (name "unconnected-(IC4-DPHY0_DP1-PadB9)") (class "Default")
      (node (ref "IC4") (pin "B9") (pinfunction "DPHY0_DP1_B9") (pintype "passive"))
    )
    (net (code "88") (name "unconnected-(IC4-DPHY0_DP2-PadB6)") (class "Default")
      (node (ref "IC4") (pin "B6") (pinfunction "DPHY0_DP2_B6") (pintype "passive"))
    )
    (net (code "89") (name "unconnected-(IC4-DPHY0_DP3-PadB10)") (class "Default")
      (node (ref "IC4") (pin "B10") (pinfunction "DPHY0_DP3_B10") (pintype "passive"))
    )
    (net (code "90") (name "unconnected-(IC4-DPHY1_DN2-PadA1)") (class "Default")
      (node (ref "IC4") (pin "A1") (pinfunction "DPHY1_DN2_A1") (pintype "passive"))
    )
    (net (code "91") (name "unconnected-(IC4-DPHY1_DN3-PadA5)") (class "Default")
      (node (ref "IC4") (pin "A5") (pinfunction "DPHY1_DN3_A5") (pintype "passive"))
    )
    (net (code "92") (name "unconnected-(IC4-DPHY1_DP2-PadB1)") (class "Default")
      (node (ref "IC4") (pin "B1") (pinfunction "DPHY1_DP2_B1") (pintype "passive"))
    )
    (net (code "93") (name "unconnected-(IC4-DPHY1_DP3-PadB5)") (class "Default")
      (node (ref "IC4") (pin "B5") (pinfunction "DPHY1_DP3_B5") (pintype "passive"))
    )
    (net (code "94") (name "unconnected-(IC4-PB6D-PadJ9)") (class "Default")
      (node (ref "IC4") (pin "J9") (pinfunction "PB6D_J9") (pintype "passive"))
    )
    (net (code "95") (name "unconnected-(IC4-PB16A-PadD9)") (class "Default")
      (node (ref "IC4") (pin "D9") (pinfunction "PB16A_D9") (pintype "passive"))
    )
    (net (code "96") (name "unconnected-(IC4-PB16D-PadJ8)") (class "Default")
      (node (ref "IC4") (pin "J8") (pinfunction "PB16D_J8") (pintype "passive"))
    )
    (net (code "97") (name "unconnected-(IC4-PB29A-PadJ7)") (class "Default")
      (node (ref "IC4") (pin "J7") (pinfunction "PB29A_J7") (pintype "passive"))
    )
    (net (code "98") (name "unconnected-(IC4-PB29D-PadJ6)") (class "Default")
      (node (ref "IC4") (pin "J6") (pinfunction "PB29D_J6") (pintype "passive"))
    )
    (net (code "99") (name "unconnected-(IC4-PB34A-PadE1)") (class "Default")
      (node (ref "IC4") (pin "E1") (pinfunction "PB34A_E1") (pintype "passive"))
    )
    (net (code "100") (name "unconnected-(IC4-PB34B-PadE2)") (class "Default")
      (node (ref "IC4") (pin "E2") (pinfunction "PB34B_E2") (pintype "passive"))
    )
    (net (code "101") (name "unconnected-(IC4-PB34D-PadJ5)") (class "Default")
      (node (ref "IC4") (pin "J5") (pinfunction "PB34D_J5") (pintype "passive"))
    )
    (net (code "102") (name "unconnected-(IC4-PB38A-PadF1)") (class "Default")
      (node (ref "IC4") (pin "F1") (pinfunction "PB38A_F1") (pintype "passive"))
    )
    (net (code "103") (name "unconnected-(IC4-PB38B-PadF2)") (class "Default")
      (node (ref "IC4") (pin "F2") (pinfunction "PB38B_F2") (pintype "passive"))
    )
    (net (code "104") (name "unconnected-(IC4-PB38D-PadJ4)") (class "Default")
      (node (ref "IC4") (pin "J4") (pinfunction "PB38D_J4") (pintype "passive"))
    )
    (net (code "105") (name "unconnected-(IC4-PB43D-PadJ3)") (class "Default")
      (node (ref "IC4") (pin "J3") (pinfunction "PB43D_J3") (pintype "passive"))
    )
    (net (code "106") (name "unconnected-(IC4-PB48-PadD1)") (class "Default")
      (node (ref "IC4") (pin "D1") (pinfunction "PB48_D1") (pintype "passive"))
    )
    (net (code "107") (name "unconnected-(IC4-PB50-PadG1)") (class "Default")
      (node (ref "IC4") (pin "G1") (pinfunction "PB50_G1") (pintype "passive"))
    )
    (net (code "108") (name "unconnected-(IC4-PB51-PadK1)") (class "Default")
      (node (ref "IC4") (pin "K1") (pinfunction "PB51_K1") (pintype "passive"))
    )
    (net (code "109") (name "unconnected-(J1-Pad12)") (class "Default")
      (node (ref "J1") (pin "12") (pinfunction "12_12") (pintype "passive"))
    )
    (net (code "110") (name "unconnected-(J1-Pad15)") (class "Default")
      (node (ref "J1") (pin "15") (pinfunction "15_15") (pintype "passive"))
    )
    (net (code "111") (name "unconnected-(J1-PadMP1)") (class "Default")
      (node (ref "J1") (pin "MP1") (pinfunction "MP1_MP1") (pintype "passive"))
    )
    (net (code "112") (name "unconnected-(J1-PadMP2)") (class "Default")
      (node (ref "J1") (pin "MP2") (pinfunction "MP2_MP2") (pintype "passive"))
    )
    (net (code "113") (name "unconnected-(U3-A9-Pad10)") (class "Default")
      (node (ref "U3") (pin "10") (pinfunction "A9_10") (pintype "bidirectional"))
    )
    (net (code "114") (name "unconnected-(U3-A10-Pad11)") (class "Default")
      (node (ref "U3") (pin "11") (pinfunction "A10_11") (pintype "bidirectional"))
    )
    (net (code "115") (name "unconnected-(U3-B9-Pad14)") (class "Default")
      (node (ref "U3") (pin "14") (pinfunction "B9_14") (pintype "bidirectional"))
    )
    (net (code "116") (name "unconnected-(U3-B10-Pad13)") (class "Default")
      (node (ref "U3") (pin "13") (pinfunction "B10_13") (pintype "bidirectional"))
    )
    (net (code "117") (name "unconnected-(U3-nc-Pad1)") (class "Default")
      (node (ref "U3") (pin "1") (pinfunction "nc_1") (pintype "passive"))
    )
    (net (code "118") (name "unconnected-(U6-nc-Pad1)") (class "Default")
      (node (ref "U6") (pin "1") (pinfunction "nc_1") (pintype "passive"))
    )
  )
)
